# AST1014.net
KiCad netlist of a schematic drawn in EAGLE
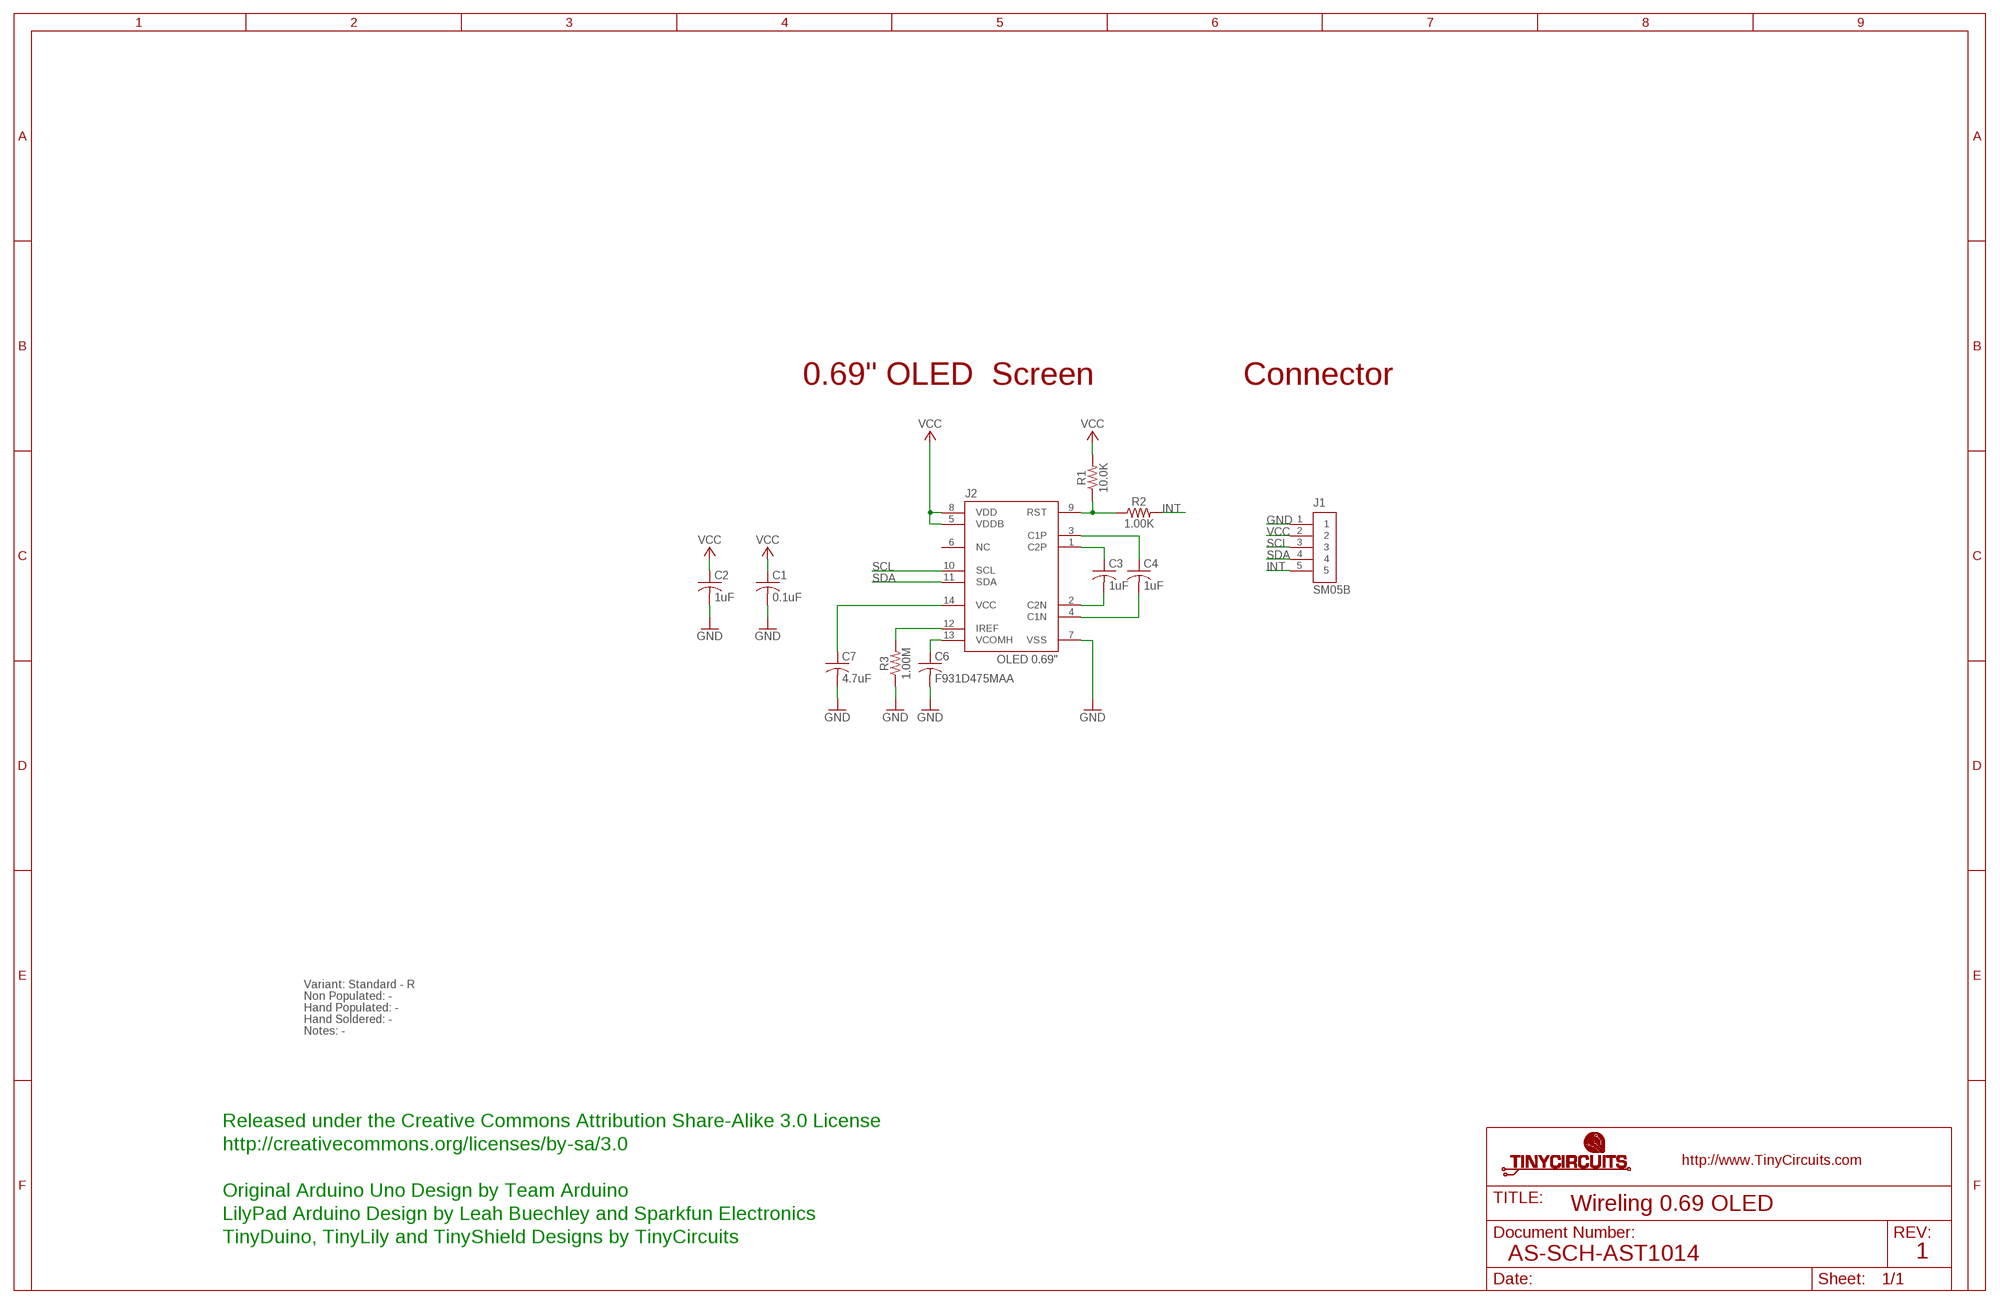
[diagram p0: schematic, sheet 1]

(export (version "E")
  (design (tool "Eeschema 10.0.6"))
  (components
    (comp (ref "C1")
      (value "0.1uF")
      (footprint "eagle-import:C0402")
      (fields (field (name "PARTNO") "AS-ITM-00008"))
      (libsource (lib "eagle-import") (part "AS-ITM-00008"))
    )
    (comp (ref "C2")
      (value "1uF")
      (footprint "eagle-import:C0603")
      (fields (field (name "PARTNO") "AS-ITM-00347") (field (name "PARTNO_1") "AS-ITM-00347"))
      (libsource (lib "eagle-import") (part "AS-ITM-00347"))
    )
    (comp (ref "C3")
      (value "1uF")
      (footprint "eagle-import:C0603")
      (fields (field (name "PARTNO") "AS-ITM-00347"))
      (libsource (lib "eagle-import") (part "AS-ITM-00347"))
    )
    (comp (ref "C4")
      (value "1uF")
      (footprint "eagle-import:C0603")
      (fields (field (name "PARTNO") "AS-ITM-00347"))
      (libsource (lib "eagle-import") (part "AS-ITM-00347"))
    )
    (comp (ref "C6")
      (value "F931D475MAA")
      (footprint "eagle-import:1206_CAP_TANT")
      (fields (field (name "PARTNO") "AS-ITM-00232"))
      (libsource (lib "eagle-import") (part "AS-ITM-00232"))
    )
    (comp (ref "C7")
      (value "4.7uF")
      (footprint "eagle-import:C0603")
      (fields (field (name "PARTNO") "AS-ITM-00088"))
      (libsource (lib "eagle-import") (part "AS-ITM-00088"))
    )
    (comp (ref "J1")
      (value "SM05B")
      (footprint "eagle-import:JST_SH_5X1")
      (fields (field (name "PARTNO") "AS-ITM-00340"))
      (libsource (lib "eagle-import") (part "AS-ITM-00340"))
    )
    (comp (ref "J2")
      (value "OLED 0.69\"")
      (footprint "eagle-import:OLED_WHITE_0.69_")
      (fields (field (name "PARTNO") "AS-ITM-00364"))
      (libsource (lib "eagle-import") (part "AS-ITM-00364"))
    )
    (comp (ref "R1")
      (value "10.0K")
      (footprint "eagle-import:0402")
      (fields (field (name "PARTNO") "AS-ITM-00032"))
      (libsource (lib "eagle-import") (part "AS-ITM-00032"))
    )
    (comp (ref "R2")
      (value "1.00K")
      (footprint "eagle-import:0402")
      (fields (field (name "PARTNO") "AS-ITM-00003") (field (name "PARTNO_1") "AS-ITM-00003"))
      (libsource (lib "eagle-import") (part "AS-ITM-00003"))
    )
    (comp (ref "R3")
      (value "1.00M")
      (footprint "eagle-import:0402")
      (fields (field (name "PARTNO") "AS-ITM-00005"))
      (libsource (lib "eagle-import") (part "AS-ITM-00005"))
    )
  )
  (nets
    (net (code "1") (name "/INT") (class "Default")
      (node (ref "J1") (pin "5") (pinfunction "5_5") (pintype "bidirectional"))
      (node (ref "R2") (pin "2") (pinfunction "2_2") (pintype "passive"))
    )
    (net (code "2") (name "/SCL") (class "Default")
      (node (ref "J1") (pin "3") (pinfunction "3_3") (pintype "bidirectional"))
      (node (ref "J2") (pin "10") (pinfunction "SCL_10") (pintype "bidirectional"))
    )
    (net (code "3") (name "/SDA") (class "Default")
      (node (ref "J1") (pin "4") (pinfunction "4_4") (pintype "bidirectional"))
      (node (ref "J2") (pin "11") (pinfunction "SDA_11") (pintype "bidirectional"))
    )
    (net (code "4") (name "GND") (class "Default")
      (node (ref "C1") (pin "2") (pinfunction "2_2") (pintype "passive"))
      (node (ref "C2") (pin "2") (pinfunction "2_2") (pintype "passive"))
      (node (ref "C6") (pin "2") (pinfunction "2_2") (pintype "passive"))
      (node (ref "C7") (pin "2") (pinfunction "2_2") (pintype "passive"))
      (node (ref "J1") (pin "1") (pinfunction "1_1") (pintype "bidirectional"))
      (node (ref "J2") (pin "7") (pinfunction "VSS_7") (pintype "bidirectional"))
      (node (ref "R3") (pin "1") (pinfunction "1_1") (pintype "passive"))
    )
    (net (code "5") (name "Net-(J2-C1N)") (class "Default")
      (node (ref "C4") (pin "2") (pinfunction "2_2") (pintype "passive"))
      (node (ref "J2") (pin "4") (pinfunction "C1N_4") (pintype "bidirectional"))
    )
    (net (code "6") (name "Net-(J2-C1P)") (class "Default")
      (node (ref "C4") (pin "1") (pinfunction "1_1") (pintype "passive"))
      (node (ref "J2") (pin "3") (pinfunction "C1P_3") (pintype "bidirectional"))
    )
    (net (code "7") (name "Net-(J2-C2N)") (class "Default")
      (node (ref "C3") (pin "2") (pinfunction "2_2") (pintype "passive"))
      (node (ref "J2") (pin "2") (pinfunction "C2N_2") (pintype "bidirectional"))
    )
    (net (code "8") (name "Net-(J2-C2P)") (class "Default")
      (node (ref "C3") (pin "1") (pinfunction "1_1") (pintype "passive"))
      (node (ref "J2") (pin "1") (pinfunction "C2P_1") (pintype "bidirectional"))
    )
    (net (code "9") (name "Net-(J2-IREF)") (class "Default")
      (node (ref "J2") (pin "12") (pinfunction "IREF_12") (pintype "bidirectional"))
      (node (ref "R3") (pin "2") (pinfunction "2_2") (pintype "passive"))
    )
    (net (code "10") (name "Net-(J2-RST)") (class "Default")
      (node (ref "J2") (pin "9") (pinfunction "RST_9") (pintype "bidirectional"))
      (node (ref "R1") (pin "1") (pinfunction "1_1") (pintype "passive"))
      (node (ref "R2") (pin "1") (pinfunction "1_1") (pintype "passive"))
    )
    (net (code "11") (name "Net-(J2-VCC)") (class "Default")
      (node (ref "C7") (pin "1") (pinfunction "1_1") (pintype "passive"))
      (node (ref "J2") (pin "14") (pinfunction "VCC_14") (pintype "bidirectional"))
    )
    (net (code "12") (name "Net-(J2-VCOMH)") (class "Default")
      (node (ref "C6") (pin "1") (pinfunction "1_1") (pintype "passive"))
      (node (ref "J2") (pin "13") (pinfunction "VCOMH_13") (pintype "bidirectional"))
    )
    (net (code "13") (name "VCC") (class "Default")
      (node (ref "C1") (pin "1") (pinfunction "1_1") (pintype "passive"))
      (node (ref "C2") (pin "1") (pinfunction "1_1") (pintype "passive"))
      (node (ref "J1") (pin "2") (pinfunction "2_2") (pintype "bidirectional"))
      (node (ref "J2") (pin "5") (pinfunction "VDDB_5") (pintype "bidirectional"))
      (node (ref "J2") (pin "8") (pinfunction "VDD_8") (pintype "bidirectional"))
      (node (ref "R1") (pin "2") (pinfunction "2_2") (pintype "passive"))
    )
    (net (code "14") (name "unconnected-(J2-NC-Pad6)") (class "Default")
      (node (ref "J2") (pin "6") (pinfunction "NC_6") (pintype "bidirectional"))
    )
  )
)
